# Initial.net
KiCad netlist of a schematic drawn in EAGLE
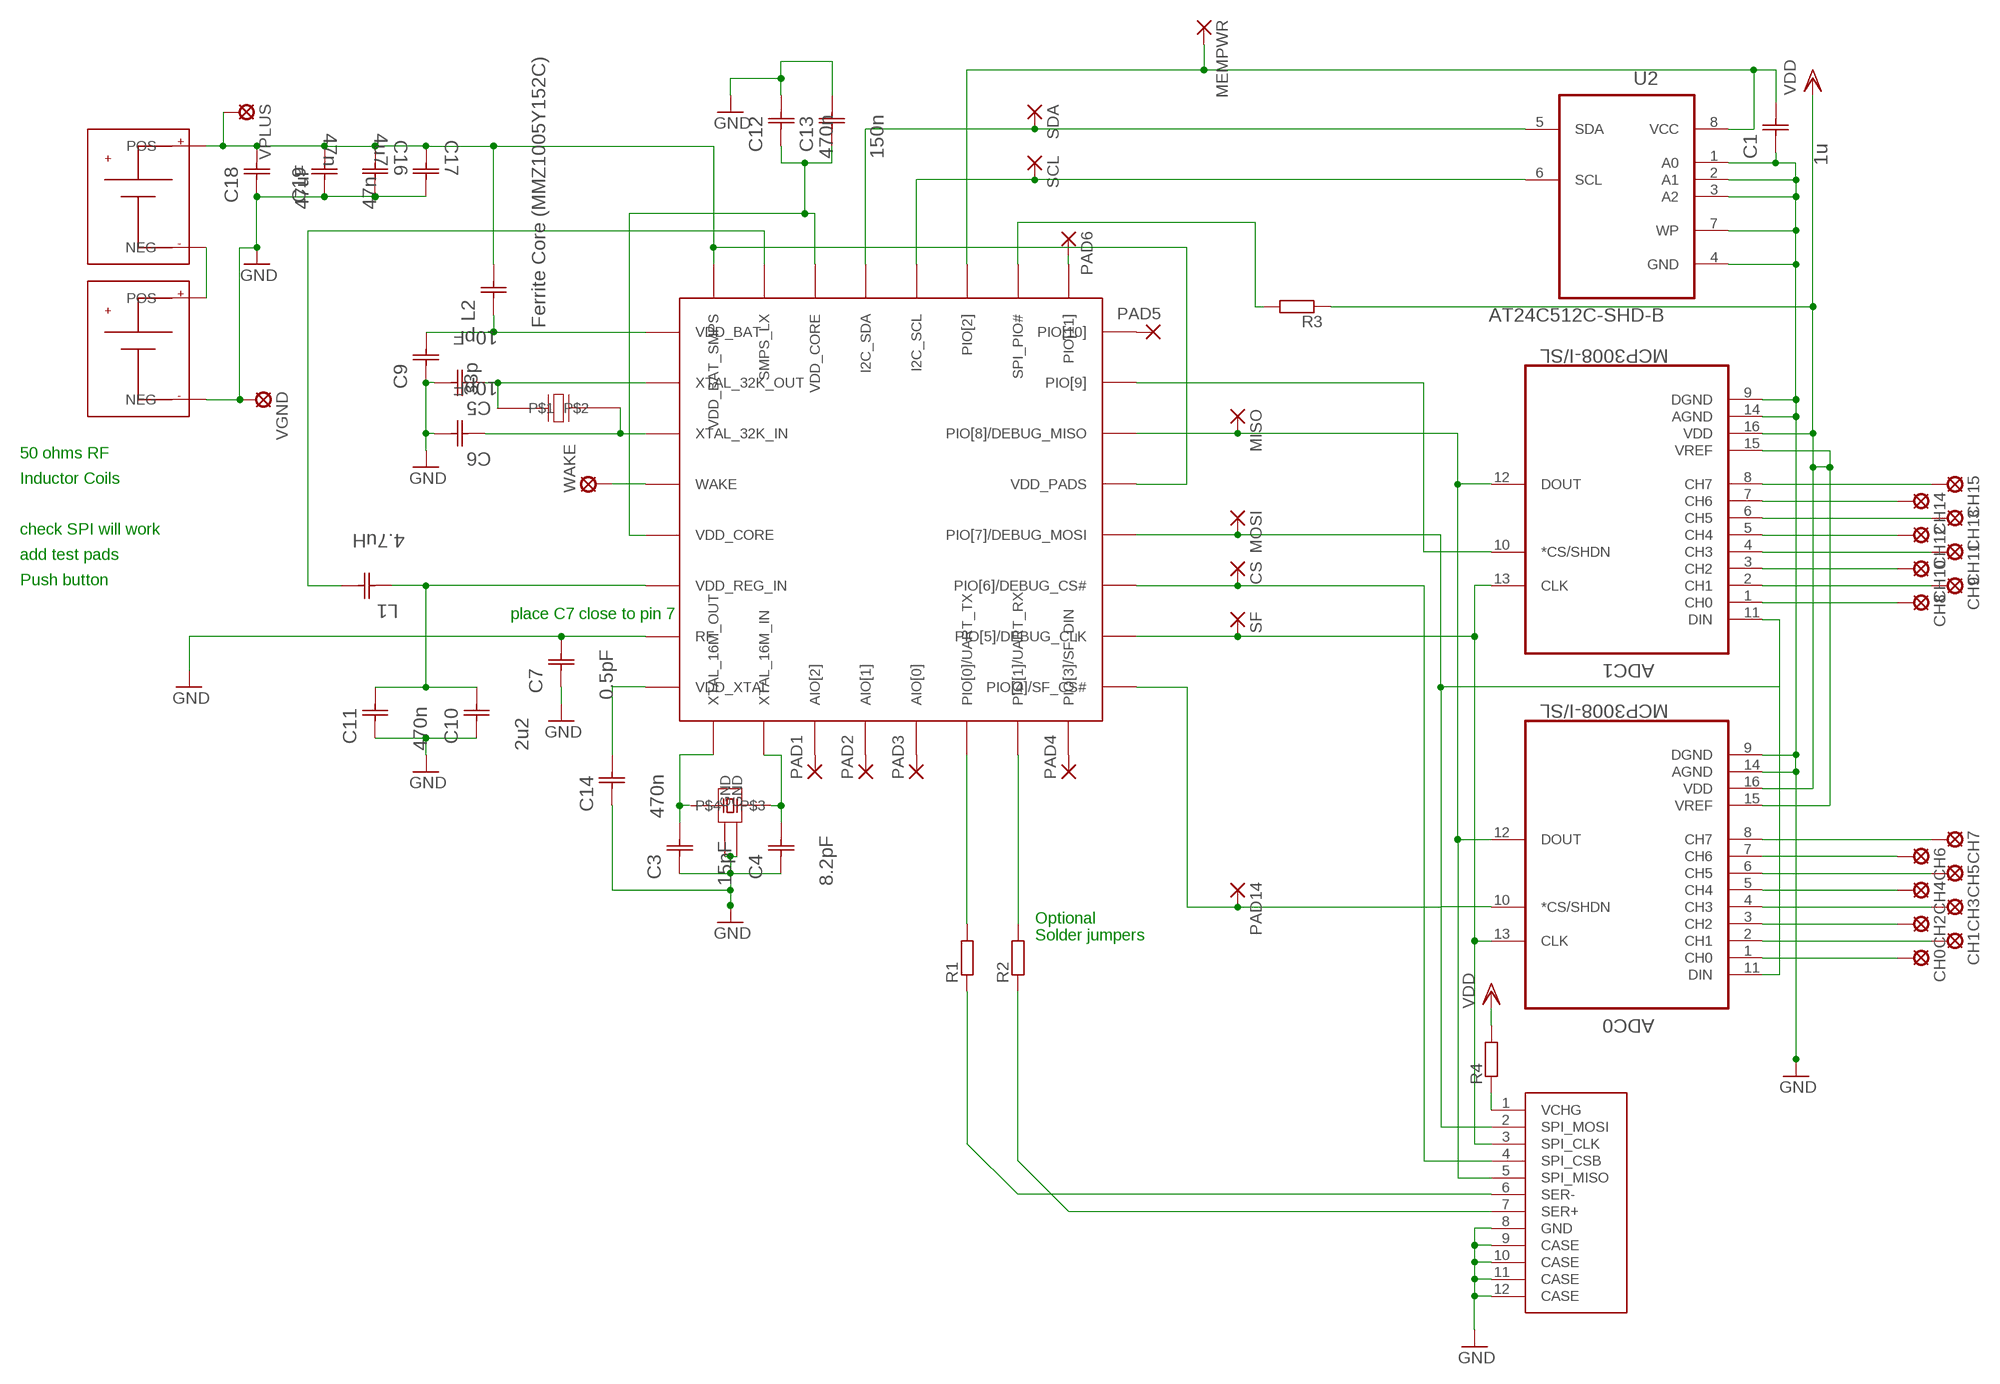
[diagram p0: schematic, sheet 1]

(export (version "E")
  (design (tool "Eeschema 10.0.6"))
  (components
    (comp (ref "ADC0")
      (value "MCP3008-I/SL")
      (footprint "eagle-import:SOIC127P600X175-16N")
      (libsource (lib "eagle-import") (part "MCP3008-I/SL"))
    )
    (comp (ref "ADC1")
      (value "MCP3008-I/SL")
      (footprint "eagle-import:SOIC127P600X175-16N")
      (libsource (lib "eagle-import") (part "MCP3008-I/SL"))
    )
    (comp (ref "C1")
      (value "1u")
      (footprint "eagle-import:CAPC1005X60N")
      (fields (field (name "MPN") "UQCL2A100JAT2A/500") (field (name "TOLERANCE") "±5%"))
      (libsource (lib "eagle-import") (part "UQCL2A100JAT2A/500"))
    )
    (comp (ref "C3")
      (value "15pF")
      (footprint "eagle-import:CAPC1005X60N")
      (fields (field (name "MPN") "UQCL2A150JAT2A/500") (field (name "TOLERANCE") "±5%"))
      (libsource (lib "eagle-import") (part "UQCL2A150JAT2A/500"))
    )
    (comp (ref "C4")
      (value "8.2pF")
      (footprint "eagle-import:CAPC1005X60N")
      (fields (field (name "MPN") "UQCL2A8R2CAT2A/500") (field (name "TOLERANCE") "±.25 pF"))
      (libsource (lib "eagle-import") (part "UQCL2A8R2CAT2A/500"))
    )
    (comp (ref "C5")
      (value "10pF")
      (footprint "eagle-import:CAPC1005X60N")
      (fields (field (name "MPN") "UQCL2A100JAT2A/500") (field (name "TOLERANCE") "±5%"))
      (libsource (lib "eagle-import") (part "UQCL2A100JAT2A/500"))
    )
    (comp (ref "C6")
      (value "10pF")
      (footprint "eagle-import:CAPC1005X60N")
      (fields (field (name "MPN") "UQCL2A100JAT2A/500") (field (name "TOLERANCE") "±5%"))
      (libsource (lib "eagle-import") (part "UQCL2A100JAT2A/500"))
    )
    (comp (ref "C7")
      (value "0.5pF")
      (footprint "eagle-import:CAPC1005X60N")
      (fields (field (name "MPN") "UQCL2A0R5BAT2A/500") (field (name "TOLERANCE") "±.1 pF"))
      (libsource (lib "eagle-import") (part "UQCL2A0R5BAT2A/500"))
    )
    (comp (ref "C9")
      (value "33p")
      (footprint "eagle-import:CAPC1005X60N")
      (fields (field (name "MPN") "UQCL2A100JAT2A/500") (field (name "TOLERANCE") "±5%"))
      (libsource (lib "eagle-import") (part "UQCL2A100JAT2A/500"))
    )
    (comp (ref "C10")
      (value "2u2")
      (footprint "eagle-import:CAPC1005X60N")
      (fields (field (name "MPN") "UQCL2A100JAT2A/500") (field (name "TOLERANCE") "±5%"))
      (libsource (lib "eagle-import") (part "UQCL2A100JAT2A/500"))
    )
    (comp (ref "C11")
      (value "470n")
      (footprint "eagle-import:CAPC1005X60N")
      (fields (field (name "MPN") "UQCL2A100JAT2A/500") (field (name "TOLERANCE") "±5%"))
      (libsource (lib "eagle-import") (part "UQCL2A100JAT2A/500"))
    )
    (comp (ref "C12")
      (value "470n")
      (footprint "eagle-import:CAPC1005X60N")
      (fields (field (name "MPN") "UQCL2A100JAT2A/500") (field (name "TOLERANCE") "±5%"))
      (libsource (lib "eagle-import") (part "UQCL2A100JAT2A/500"))
    )
    (comp (ref "C13")
      (value "150n")
      (footprint "eagle-import:CAPC1005X60N")
      (fields (field (name "MPN") "UQCL2A100JAT2A/500") (field (name "TOLERANCE") "±5%"))
      (libsource (lib "eagle-import") (part "UQCL2A100JAT2A/500"))
    )
    (comp (ref "C14")
      (value "470n")
      (footprint "eagle-import:CAPC1005X60N")
      (fields (field (name "MPN") "UQCL2A100JAT2A/500") (field (name "TOLERANCE") "±5%"))
      (libsource (lib "eagle-import") (part "UQCL2A100JAT2A/500"))
    )
    (comp (ref "C16")
      (value "47n")
      (footprint "eagle-import:CAPC1005X60N")
      (fields (field (name "MPN") "UQCL2A1R0BAT2A/500") (field (name "TOLERANCE") "±.1 pF"))
      (libsource (lib "eagle-import") (part "UQCL2A1R0BAT2A/500"))
    )
    (comp (ref "C17")
      (value "4u7")
      (footprint "eagle-import:CAPC1005X60N")
      (fields (field (name "MPN") "UQCL2A1R0BAT2A/500") (field (name "TOLERANCE") "±.1 pF"))
      (libsource (lib "eagle-import") (part "UQCL2A1R0BAT2A/500"))
    )
    (comp (ref "C18")
      (value "47uF")
      (footprint "eagle-import:CAPC2012X130N")
      (fields (field (name "MPN") "0805AA100MAT1A") (field (name "TOLERANCE") "±20%"))
      (libsource (lib "eagle-import") (part "0805AA100MAT1A"))
    )
    (comp (ref "C19")
      (value "47n")
      (footprint "eagle-import:CAPC2012X130N")
      (fields (field (name "MPN") "0805AA100MAT1A") (field (name "TOLERANCE") "±20%"))
      (libsource (lib "eagle-import") (part "0805AA100MAT1A"))
    )
    (comp (ref "CH0")
      (value "LSP10")
      (footprint "eagle-import:LSP10")
      (libsource (lib "eagle-import") (part "LSP10"))
    )
    (comp (ref "CH1")
      (value "LSP10")
      (footprint "eagle-import:LSP10")
      (libsource (lib "eagle-import") (part "LSP10"))
    )
    (comp (ref "CH2")
      (value "LSP10")
      (footprint "eagle-import:LSP10")
      (libsource (lib "eagle-import") (part "LSP10"))
    )
    (comp (ref "CH3")
      (value "LSP10")
      (footprint "eagle-import:LSP10")
      (libsource (lib "eagle-import") (part "LSP10"))
    )
    (comp (ref "CH4")
      (value "LSP10")
      (footprint "eagle-import:LSP10")
      (libsource (lib "eagle-import") (part "LSP10"))
    )
    (comp (ref "CH5")
      (value "LSP10")
      (footprint "eagle-import:LSP10")
      (libsource (lib "eagle-import") (part "LSP10"))
    )
    (comp (ref "CH6")
      (value "LSP10")
      (footprint "eagle-import:LSP10")
      (libsource (lib "eagle-import") (part "LSP10"))
    )
    (comp (ref "CH7")
      (value "LSP10")
      (footprint "eagle-import:LSP10")
      (libsource (lib "eagle-import") (part "LSP10"))
    )
    (comp (ref "CH8")
      (value "LSP10")
      (footprint "eagle-import:LSP10")
      (libsource (lib "eagle-import") (part "LSP10"))
    )
    (comp (ref "CH9")
      (value "LSP10")
      (footprint "eagle-import:LSP10")
      (libsource (lib "eagle-import") (part "LSP10"))
    )
    (comp (ref "CH10")
      (value "LSP10")
      (footprint "eagle-import:LSP10")
      (libsource (lib "eagle-import") (part "LSP10"))
    )
    (comp (ref "CH11")
      (value "LSP10")
      (footprint "eagle-import:LSP10")
      (libsource (lib "eagle-import") (part "LSP10"))
    )
    (comp (ref "CH12")
      (value "LSP10")
      (footprint "eagle-import:LSP10")
      (libsource (lib "eagle-import") (part "LSP10"))
    )
    (comp (ref "CH13")
      (value "LSP10")
      (footprint "eagle-import:LSP10")
      (libsource (lib "eagle-import") (part "LSP10"))
    )
    (comp (ref "CH14")
      (value "LSP10")
      (footprint "eagle-import:LSP10")
      (libsource (lib "eagle-import") (part "LSP10"))
    )
    (comp (ref "CH15")
      (value "LSP10")
      (footprint "eagle-import:LSP10")
      (libsource (lib "eagle-import") (part "LSP10"))
    )
    (comp (ref "CS")
      (value "1,6/0,8")
      (footprint "eagle-import:1,6_0,8")
      (libsource (lib "eagle-import") (part "1,6/0,8"))
    )
    (comp (ref "L1")
      (value "4.7uH")
      (footprint "eagle-import:CAPC3225X127N")
      (fields (field (name "MPN") "12107C102JAT2A") (field (name "TOLERANCE") "±5%"))
      (libsource (lib "eagle-import") (part "12107C102JAT2A"))
    )
    (comp (ref "L2")
      (value "Ferrite Core (MMZ1005Y152C)")
      (footprint "eagle-import:CAPC1005X60N")
      (fields (field (name "MPN") "UQCL2A100JAT2A/500") (field (name "TOLERANCE") "±5%"))
      (libsource (lib "eagle-import") (part "UQCL2A100JAT2A/500"))
    )
    (comp (ref "MEMPWR")
      (value "1,6/0,8")
      (footprint "eagle-import:1,6_0,8")
      (libsource (lib "eagle-import") (part "1,6/0,8"))
    )
    (comp (ref "MISO")
      (value "1,6/0,8")
      (footprint "eagle-import:1,6_0,8")
      (libsource (lib "eagle-import") (part "1,6/0,8"))
    )
    (comp (ref "MOSI")
      (value "1,6/0,8")
      (footprint "eagle-import:1,6_0,8")
      (libsource (lib "eagle-import") (part "1,6/0,8"))
    )
    (comp (ref "PAD1")
      (value "1,6/0,8")
      (footprint "eagle-import:1,6_0,8")
      (libsource (lib "eagle-import") (part "1,6/0,8"))
    )
    (comp (ref "PAD2")
      (value "1,6/0,8")
      (footprint "eagle-import:1,6_0,8")
      (libsource (lib "eagle-import") (part "1,6/0,8"))
    )
    (comp (ref "PAD3")
      (value "1,6/0,8")
      (footprint "eagle-import:1,6_0,8")
      (libsource (lib "eagle-import") (part "1,6/0,8"))
    )
    (comp (ref "PAD4")
      (value "1,6/0,8")
      (footprint "eagle-import:1,6_0,8")
      (libsource (lib "eagle-import") (part "1,6/0,8"))
    )
    (comp (ref "PAD5")
      (value "1,6/0,8")
      (footprint "eagle-import:1,6_0,8")
      (libsource (lib "eagle-import") (part "1,6/0,8"))
    )
    (comp (ref "PAD6")
      (value "1,6/0,8")
      (footprint "eagle-import:1,6_0,8")
      (libsource (lib "eagle-import") (part "1,6/0,8"))
    )
    (comp (ref "PAD14")
      (value "1,6/0,8")
      (footprint "eagle-import:1,6_0,8")
      (libsource (lib "eagle-import") (part "1,6/0,8"))
    )
    (comp (ref "R1")
      (value "BVS")
      (footprint "eagle-import:BVS")
      (libsource (lib "eagle-import") (part "BVS"))
    )
    (comp (ref "R2")
      (value "BVS")
      (footprint "eagle-import:BVS")
      (libsource (lib "eagle-import") (part "BVS"))
    )
    (comp (ref "R3")
      (value "BVS")
      (footprint "eagle-import:BVS")
      (libsource (lib "eagle-import") (part "BVS"))
    )
    (comp (ref "R4")
      (value "BVS")
      (footprint "eagle-import:BVS")
      (libsource (lib "eagle-import") (part "BVS"))
    )
    (comp (ref "SCL")
      (value "1,6/0,8")
      (footprint "eagle-import:1,6_0,8")
      (libsource (lib "eagle-import") (part "1,6/0,8"))
    )
    (comp (ref "SDA")
      (value "1,6/0,8")
      (footprint "eagle-import:1,6_0,8")
      (libsource (lib "eagle-import") (part "1,6/0,8"))
    )
    (comp (ref "SF")
      (value "1,6/0,8")
      (footprint "eagle-import:1,6_0,8")
      (libsource (lib "eagle-import") (part "1,6/0,8"))
    )
    (comp (ref "U$1")
      (value "CSR1010A05-IQQM-R")
      (footprint "eagle-import:CSR1010A05-IQQM-R")
      (libsource (lib "eagle-import") (part "CSR1010A05-IQQM-R"))
    )
    (comp (ref "U$2")
      (value "8PIN_SMT_CONNECTOR")
      (footprint "eagle-import:8PIN_SMT_CONNECTOR")
      (libsource (lib "eagle-import") (part "8PIN_SMT_CONNECTOR"))
    )
    (comp (ref "U$3")
      (value "TSX3225")
      (footprint "eagle-import:TSX3225")
      (libsource (lib "eagle-import") (part "TSX3225"))
    )
    (comp (ref "U$4")
      (value "SSP-T7-F")
      (footprint "eagle-import:SSP-T7-F")
      (libsource (lib "eagle-import") (part "SSP-T7-F"))
    )
    (comp (ref "U$5")
      (value "BATTERY_2996")
      (footprint "eagle-import:BATTERY_2996")
      (libsource (lib "eagle-import") (part "BATTERY_2996"))
    )
    (comp (ref "U$6")
      (value "BATTERY_2996")
      (footprint "eagle-import:BATTERY_2996")
      (libsource (lib "eagle-import") (part "BATTERY_2996"))
    )
    (comp (ref "U2")
      (value "AT24C512C-SHD-B")
      (footprint "eagle-import:SOIC127P798X216-8N")
      (libsource (lib "eagle-import") (part "AT24C512C-SHD-B"))
    )
    (comp (ref "VGND")
      (value "LSP10")
      (footprint "eagle-import:LSP10")
      (libsource (lib "eagle-import") (part "LSP10"))
    )
    (comp (ref "VPLUS")
      (value "Vrail")
      (footprint "eagle-import:LSP10")
      (libsource (lib "eagle-import") (part "LSP10"))
    )
    (comp (ref "WAKE")
      (value "Vrail")
      (footprint "eagle-import:LSP10")
      (libsource (lib "eagle-import") (part "LSP10"))
    )
  )
  (nets
    (net (code "1") (name "/VCC") (class "Default")
      (node (ref "U2") (pin "8") (pinfunction "VCC_8") (pintype "power_in"))
    )
    (net (code "2") (name "GND") (class "Default")
      (node (ref "ADC0") (pin "14") (pinfunction "AGND_14") (pintype "passive"))
      (node (ref "ADC0") (pin "9") (pinfunction "DGND_9") (pintype "passive"))
      (node (ref "ADC1") (pin "14") (pinfunction "AGND_14") (pintype "passive"))
      (node (ref "ADC1") (pin "9") (pinfunction "DGND_9") (pintype "passive"))
      (node (ref "C1") (pin "2") (pinfunction "C1_2") (pintype "passive"))
      (node (ref "C10") (pin "2") (pinfunction "C1_2") (pintype "passive"))
      (node (ref "C11") (pin "2") (pinfunction "C1_2") (pintype "passive"))
      (node (ref "C12") (pin "1") (pinfunction "C2_1") (pintype "passive"))
      (node (ref "C13") (pin "1") (pinfunction "C2_1") (pintype "passive"))
      (node (ref "C14") (pin "2") (pinfunction "C1_2") (pintype "passive"))
      (node (ref "C16") (pin "1") (pinfunction "C2_1") (pintype "passive"))
      (node (ref "C17") (pin "1") (pinfunction "C2_1") (pintype "passive"))
      (node (ref "C18") (pin "1") (pinfunction "C1_1") (pintype "passive"))
      (node (ref "C19") (pin "1") (pinfunction "C1_1") (pintype "passive"))
      (node (ref "C3") (pin "2") (pinfunction "C1_2") (pintype "passive"))
      (node (ref "C4") (pin "2") (pinfunction "C1_2") (pintype "passive"))
      (node (ref "C5") (pin "1") (pinfunction "C2_1") (pintype "passive"))
      (node (ref "C6") (pin "1") (pinfunction "C2_1") (pintype "passive"))
      (node (ref "C7") (pin "1") (pinfunction "C2_1") (pintype "passive"))
      (node (ref "C7") (pin "2") (pinfunction "C1_2") (pintype "passive"))
      (node (ref "C9") (pin "2") (pinfunction "C1_2") (pintype "passive"))
      (node (ref "U$1") (pin "RF") (pinfunction "RF_RF") (pintype "output"))
      (node (ref "U$2") (pin "10") (pinfunction "CASE_10") (pintype "bidirectional"))
      (node (ref "U$2") (pin "11") (pinfunction "CASE_11") (pintype "bidirectional"))
      (node (ref "U$2") (pin "12") (pinfunction "CASE_12") (pintype "bidirectional"))
      (node (ref "U$2") (pin "8") (pinfunction "GND_8") (pintype "bidirectional"))
      (node (ref "U$2") (pin "9") (pinfunction "CASE_9") (pintype "bidirectional"))
      (node (ref "U$3") (pin "2") (pinfunction "GND_2") (pintype "bidirectional"))
      (node (ref "U$3") (pin "4") (pinfunction "GND_4") (pintype "bidirectional"))
      (node (ref "U$6") (pin "NEG") (pinfunction "NEG_NEG") (pintype "bidirectional"))
      (node (ref "U2") (pin "1") (pinfunction "A0_1") (pintype "input"))
      (node (ref "U2") (pin "2") (pinfunction "A1_2") (pintype "input"))
      (node (ref "U2") (pin "3") (pinfunction "A2_3") (pintype "input"))
      (node (ref "U2") (pin "4") (pinfunction "GND_4") (pintype "power_in"))
      (node (ref "U2") (pin "7") (pinfunction "WP_7") (pintype "input"))
      (node (ref "VGND") (pin "MP") (pinfunction "MP_MP") (pintype "passive"))
    )
    (net (code "3") (name "Net-(ADC0-*CS{slash}SHDN)") (class "Default")
      (node (ref "ADC0") (pin "10") (pinfunction "*CS/SHDN_10") (pintype "input"))
      (node (ref "PAD14") (pin "1") (pinfunction "P_1") (pintype "passive"))
      (node (ref "U$1") (pin "PIO[4]/SF_CS#") (pinfunction "PIO[4]/SF_CS#_PIO[4]/SF_CS#") (pintype "output"))
    )
    (net (code "4") (name "Net-(ADC0-CH0)") (class "Default")
      (node (ref "ADC0") (pin "1") (pinfunction "CH0_1") (pintype "input"))
      (node (ref "CH0") (pin "MP") (pinfunction "MP_MP") (pintype "passive"))
    )
    (net (code "5") (name "Net-(ADC0-CH1)") (class "Default")
      (node (ref "ADC0") (pin "2") (pinfunction "CH1_2") (pintype "input"))
      (node (ref "CH1") (pin "MP") (pinfunction "MP_MP") (pintype "passive"))
    )
    (net (code "6") (name "Net-(ADC0-CH2)") (class "Default")
      (node (ref "ADC0") (pin "3") (pinfunction "CH2_3") (pintype "input"))
      (node (ref "CH2") (pin "MP") (pinfunction "MP_MP") (pintype "passive"))
    )
    (net (code "7") (name "Net-(ADC0-CH3)") (class "Default")
      (node (ref "ADC0") (pin "4") (pinfunction "CH3_4") (pintype "input"))
      (node (ref "CH3") (pin "MP") (pinfunction "MP_MP") (pintype "passive"))
    )
    (net (code "8") (name "Net-(ADC0-CH4)") (class "Default")
      (node (ref "ADC0") (pin "5") (pinfunction "CH4_5") (pintype "input"))
      (node (ref "CH4") (pin "MP") (pinfunction "MP_MP") (pintype "passive"))
    )
    (net (code "9") (name "Net-(ADC0-CH5)") (class "Default")
      (node (ref "ADC0") (pin "6") (pinfunction "CH5_6") (pintype "input"))
      (node (ref "CH5") (pin "MP") (pinfunction "MP_MP") (pintype "passive"))
    )
    (net (code "10") (name "Net-(ADC0-CH6)") (class "Default")
      (node (ref "ADC0") (pin "7") (pinfunction "CH6_7") (pintype "input"))
      (node (ref "CH6") (pin "MP") (pinfunction "MP_MP") (pintype "passive"))
    )
    (net (code "11") (name "Net-(ADC0-CH7)") (class "Default")
      (node (ref "ADC0") (pin "8") (pinfunction "CH7_8") (pintype "input"))
      (node (ref "CH7") (pin "MP") (pinfunction "MP_MP") (pintype "passive"))
    )
    (net (code "12") (name "Net-(ADC0-CLK)") (class "Default")
      (node (ref "ADC0") (pin "13") (pinfunction "CLK_13") (pintype "input"))
      (node (ref "ADC1") (pin "13") (pinfunction "CLK_13") (pintype "input"))
      (node (ref "SF") (pin "1") (pinfunction "P_1") (pintype "passive"))
      (node (ref "U$1") (pin "PIO[5]/DEBUG_CLK") (pinfunction "PIO[5]/DEBUG_CLK_PIO[5]/DEBUG_CLK") (pintype "output"))
      (node (ref "U$2") (pin "3") (pinfunction "SPI_CLK_3") (pintype "bidirectional"))
    )
    (net (code "13") (name "Net-(ADC0-DIN)") (class "Default")
      (node (ref "ADC0") (pin "11") (pinfunction "DIN_11") (pintype "input"))
      (node (ref "ADC1") (pin "11") (pinfunction "DIN_11") (pintype "input"))
      (node (ref "MOSI") (pin "1") (pinfunction "P_1") (pintype "passive"))
      (node (ref "U$1") (pin "PIO[7]/DEBUG_MOSI") (pinfunction "PIO[7]/DEBUG_MOSI_PIO[7]/DEBUG_MOSI") (pintype "output"))
      (node (ref "U$2") (pin "2") (pinfunction "SPI_MOSI_2") (pintype "bidirectional"))
    )
    (net (code "14") (name "Net-(ADC0-DOUT)") (class "Default")
      (node (ref "ADC0") (pin "12") (pinfunction "DOUT_12") (pintype "output"))
      (node (ref "ADC1") (pin "12") (pinfunction "DOUT_12") (pintype "output"))
      (node (ref "MISO") (pin "1") (pinfunction "P_1") (pintype "passive"))
      (node (ref "U$1") (pin "PIO[8]/DEBUG_MISO") (pinfunction "PIO[8]/DEBUG_MISO_PIO[8]/DEBUG_MISO") (pintype "output"))
      (node (ref "U$2") (pin "5") (pinfunction "SPI_MISO_5") (pintype "bidirectional"))
    )
    (net (code "15") (name "Net-(ADC1-*CS{slash}SHDN)") (class "Default")
      (node (ref "ADC1") (pin "10") (pinfunction "*CS/SHDN_10") (pintype "input"))
      (node (ref "U$1") (pin "PIO[9]") (pinfunction "PIO[9]_PIO[9]") (pintype "output"))
    )
    (net (code "16") (name "Net-(ADC1-CH0)") (class "Default")
      (node (ref "ADC1") (pin "1") (pinfunction "CH0_1") (pintype "input"))
      (node (ref "CH8") (pin "MP") (pinfunction "MP_MP") (pintype "passive"))
    )
    (net (code "17") (name "Net-(ADC1-CH1)") (class "Default")
      (node (ref "ADC1") (pin "2") (pinfunction "CH1_2") (pintype "input"))
      (node (ref "CH9") (pin "MP") (pinfunction "MP_MP") (pintype "passive"))
    )
    (net (code "18") (name "Net-(ADC1-CH2)") (class "Default")
      (node (ref "ADC1") (pin "3") (pinfunction "CH2_3") (pintype "input"))
      (node (ref "CH10") (pin "MP") (pinfunction "MP_MP") (pintype "passive"))
    )
    (net (code "19") (name "Net-(ADC1-CH3)") (class "Default")
      (node (ref "ADC1") (pin "4") (pinfunction "CH3_4") (pintype "input"))
      (node (ref "CH11") (pin "MP") (pinfunction "MP_MP") (pintype "passive"))
    )
    (net (code "20") (name "Net-(ADC1-CH4)") (class "Default")
      (node (ref "ADC1") (pin "5") (pinfunction "CH4_5") (pintype "input"))
      (node (ref "CH12") (pin "MP") (pinfunction "MP_MP") (pintype "passive"))
    )
    (net (code "21") (name "Net-(ADC1-CH5)") (class "Default")
      (node (ref "ADC1") (pin "6") (pinfunction "CH5_6") (pintype "input"))
      (node (ref "CH13") (pin "MP") (pinfunction "MP_MP") (pintype "passive"))
    )
    (net (code "22") (name "Net-(ADC1-CH6)") (class "Default")
      (node (ref "ADC1") (pin "7") (pinfunction "CH6_7") (pintype "input"))
      (node (ref "CH14") (pin "MP") (pinfunction "MP_MP") (pintype "passive"))
    )
    (net (code "23") (name "Net-(ADC1-CH7)") (class "Default")
      (node (ref "ADC1") (pin "8") (pinfunction "CH7_8") (pintype "input"))
      (node (ref "CH15") (pin "MP") (pinfunction "MP_MP") (pintype "passive"))
    )
    (net (code "24") (name "Net-(C1-C2)") (class "Default")
      (node (ref "C1") (pin "1") (pinfunction "C2_1") (pintype "passive"))
      (node (ref "MEMPWR") (pin "1") (pinfunction "P_1") (pintype "passive"))
      (node (ref "U$1") (pin "PIO[2]") (pinfunction "PIO[2]_PIO[2]") (pintype "output"))
    )
    (net (code "25") (name "Net-(C3-C2)") (class "Default")
      (node (ref "C3") (pin "1") (pinfunction "C2_1") (pintype "passive"))
      (node (ref "U$1") (pin "XTAL_16M_OUT") (pinfunction "XTAL_16M_OUT_XTAL_16M_OUT") (pintype "output"))
    )
    (net (code "26") (name "Net-(C4-C2)") (class "Default")
      (node (ref "C4") (pin "1") (pinfunction "C2_1") (pintype "passive"))
      (node (ref "U$1") (pin "XTAL_16M_IN") (pinfunction "XTAL_16M_IN_XTAL_16M_IN") (pintype "output"))
    )
    (net (code "27") (name "Net-(C5-C1)") (class "Default")
      (node (ref "C5") (pin "2") (pinfunction "C1_2") (pintype "passive"))
      (node (ref "U$1") (pin "XTAL_32K_OUT") (pinfunction "XTAL_32K_OUT_XTAL_32K_OUT") (pintype "output"))
    )
    (net (code "28") (name "Net-(C6-C1)") (class "Default")
      (node (ref "C6") (pin "2") (pinfunction "C1_2") (pintype "passive"))
      (node (ref "U$1") (pin "XTAL_32K_IN") (pinfunction "XTAL_32K_IN_XTAL_32K_IN") (pintype "output"))
      (node (ref "U$4") (pin "1") (pinfunction "P$1_1") (pintype "bidirectional"))
    )
    (net (code "29") (name "Net-(C9-C2)") (class "Default")
      (node (ref "C9") (pin "1") (pinfunction "C2_1") (pintype "passive"))
      (node (ref "L2") (pin "2") (pinfunction "C1_2") (pintype "passive"))
      (node (ref "U$1") (pin "VDD_BAT") (pinfunction "VDD_BAT_VDD_BAT") (pintype "output"))
    )
    (net (code "30") (name "Net-(C10-C2)") (class "Default")
      (node (ref "C10") (pin "1") (pinfunction "C2_1") (pintype "passive"))
      (node (ref "C11") (pin "1") (pinfunction "C2_1") (pintype "passive"))
      (node (ref "L1") (pin "1") (pinfunction "C1_1") (pintype "passive"))
      (node (ref "U$1") (pin "VDD_REG_IN") (pinfunction "VDD_REG_IN_VDD_REG_IN") (pintype "output"))
    )
    (net (code "31") (name "Net-(C12-C1)") (class "Default")
      (node (ref "C12") (pin "2") (pinfunction "C1_2") (pintype "passive"))
      (node (ref "C13") (pin "2") (pinfunction "C1_2") (pintype "passive"))
      (node (ref "U$1") (pin "VDD_CORE") (pinfunction "VDD_CORE_VDD_CORE") (pintype "output"))
      (node (ref "U$1") (pin "VDD_CORE@1") (pinfunction "VDD_CORE_VDD_CORE@1") (pintype "bidirectional"))
    )
    (net (code "32") (name "Net-(C14-C2)") (class "Default")
      (node (ref "C14") (pin "1") (pinfunction "C2_1") (pintype "passive"))
      (node (ref "U$1") (pin "VDD_XTAL") (pinfunction "VDD_XTAL_VDD_XTAL") (pintype "output"))
    )
    (net (code "33") (name "Net-(C16-C1)") (class "Default")
      (node (ref "C16") (pin "2") (pinfunction "C1_2") (pintype "passive"))
      (node (ref "C17") (pin "2") (pinfunction "C1_2") (pintype "passive"))
      (node (ref "C18") (pin "2") (pinfunction "C2_2") (pintype "passive"))
      (node (ref "C19") (pin "2") (pinfunction "C2_2") (pintype "passive"))
      (node (ref "L2") (pin "1") (pinfunction "C2_1") (pintype "passive"))
      (node (ref "U$1") (pin "VDD_BAT_SMPS") (pinfunction "VDD_BAT_SMPS_VDD_BAT_SMPS") (pintype "output"))
      (node (ref "U$1") (pin "VDD_PADS") (pinfunction "VDD_PADS_VDD_PADS") (pintype "output"))
      (node (ref "U$5") (pin "POS@1") (pinfunction "POS_POS@1") (pintype "bidirectional"))
      (node (ref "VPLUS") (pin "MP") (pinfunction "MP_MP") (pintype "passive"))
    )
    (net (code "34") (name "Net-(CS-P)") (class "Default")
      (node (ref "CS") (pin "1") (pinfunction "P_1") (pintype "passive"))
      (node (ref "U$1") (pin "PIO[6]/DEBUG_CS#") (pinfunction "PIO[6]/DEBUG_CS#_PIO[6]/DEBUG_CS#") (pintype "output"))
      (node (ref "U$2") (pin "4") (pinfunction "SPI_CSB_4") (pintype "bidirectional"))
    )
    (net (code "35") (name "Net-(L1-C2)") (class "Default")
      (node (ref "L1") (pin "2") (pinfunction "C2_2") (pintype "passive"))
      (node (ref "U$1") (pin "SMPS_LX") (pinfunction "SMPS_LX_SMPS_LX") (pintype "output"))
    )
    (net (code "36") (name "Net-(PAD1-P)") (class "Default")
      (node (ref "PAD1") (pin "1") (pinfunction "P_1") (pintype "passive"))
      (node (ref "U$1") (pin "AIO[2]") (pinfunction "AIO[2]_AIO[2]") (pintype "output"))
    )
    (net (code "37") (name "Net-(PAD2-P)") (class "Default")
      (node (ref "PAD2") (pin "1") (pinfunction "P_1") (pintype "passive"))
      (node (ref "U$1") (pin "AIO[1]") (pinfunction "AIO[1]_AIO[1]") (pintype "output"))
    )
    (net (code "38") (name "Net-(PAD3-P)") (class "Default")
      (node (ref "PAD3") (pin "1") (pinfunction "P_1") (pintype "passive"))
      (node (ref "U$1") (pin "AIO[0]") (pinfunction "AIO[0]_AIO[0]") (pintype "output"))
    )
    (net (code "39") (name "Net-(PAD4-P)") (class "Default")
      (node (ref "PAD4") (pin "1") (pinfunction "P_1") (pintype "passive"))
      (node (ref "U$1") (pin "PIO[3]/SF_DIN") (pinfunction "PIO[3]/SF_DIN_PIO[3]/SF_DIN") (pintype "output"))
    )
    (net (code "40") (name "Net-(PAD5-P)") (class "Default")
      (node (ref "PAD5") (pin "1") (pinfunction "P_1") (pintype "passive"))
      (node (ref "U$1") (pin "PIO[10]") (pinfunction "PIO[10]_PIO[10]") (pintype "output"))
    )
    (net (code "41") (name "Net-(PAD6-P)") (class "Default")
      (node (ref "PAD6") (pin "1") (pinfunction "P_1") (pintype "passive"))
      (node (ref "U$1") (pin "PIO[11]") (pinfunction "PIO[11]_PIO[11]") (pintype "output"))
    )
    (net (code "42") (name "Net-(R1-Pad1)") (class "Default")
      (node (ref "R1") (pin "1") (pinfunction "1_1") (pintype "passive"))
      (node (ref "U$1") (pin "PIO[0]/UART_TX") (pinfunction "PIO[0]/UART_TX_PIO[0]/UART_TX") (pintype "output"))
    )
    (net (code "43") (name "Net-(R2-Pad1)") (class "Default")
      (node (ref "R2") (pin "1") (pinfunction "1_1") (pintype "passive"))
      (node (ref "U$1") (pin "PIO[1]/UART_RX") (pinfunction "PIO[1]/UART_RX_PIO[1]/UART_RX") (pintype "output"))
    )
    (net (code "44") (name "Net-(R3-Pad1)") (class "Default")
      (node (ref "R3") (pin "1") (pinfunction "1_1") (pintype "passive"))
      (node (ref "U$1") (pin "SPI_PIO#") (pinfunction "SPI_PIO#_SPI_PIO#") (pintype "output"))
    )
    (net (code "45") (name "Net-(SCL-P)") (class "Default")
      (node (ref "SCL") (pin "1") (pinfunction "P_1") (pintype "passive"))
      (node (ref "U$1") (pin "I2C_SCL") (pinfunction "I2C_SCL_I2C_SCL") (pintype "output"))
      (node (ref "U2") (pin "6") (pinfunction "SCL_6") (pintype "input"))
    )
    (net (code "46") (name "Net-(SDA-P)") (class "Default")
      (node (ref "SDA") (pin "1") (pinfunction "P_1") (pintype "passive"))
      (node (ref "U$1") (pin "I2C_SDA") (pinfunction "I2C_SDA_I2C_SDA") (pintype "output"))
      (node (ref "U2") (pin "5") (pinfunction "SDA_5") (pintype "bidirectional"))
    )
    (net (code "47") (name "Net-(U$1-PadWAKE)") (class "Default")
      (node (ref "U$1") (pin "WAKE") (pinfunction "WAKE_WAKE") (pintype "output"))
      (node (ref "WAKE") (pin "MP") (pinfunction "MP_MP") (pintype "passive"))
    )
    (net (code "48") (name "Net-(U$2-SER+)") (class "Default")
      (node (ref "R2") (pin "2") (pinfunction "2_2") (pintype "passive"))
      (node (ref "U$2") (pin "7") (pinfunction "SER+_7") (pintype "bidirectional"))
    )
    (net (code "49") (name "Net-(U$2-SER-)") (class "Default")
      (node (ref "R1") (pin "2") (pinfunction "2_2") (pintype "passive"))
      (node (ref "U$2") (pin "6") (pinfunction "SER-_6") (pintype "bidirectional"))
    )
    (net (code "50") (name "Net-(U$2-VCHG)") (class "Default")
      (node (ref "R4") (pin "2") (pinfunction "2_2") (pintype "passive"))
      (node (ref "U$2") (pin "1") (pinfunction "VCHG_1") (pintype "bidirectional"))
    )
    (net (code "51") (name "Net-(U$6-POS)") (class "Default")
      (node (ref "U$5") (pin "NEG") (pinfunction "NEG_NEG") (pintype "bidirectional"))
      (node (ref "U$6") (pin "POS@1") (pinfunction "POS_POS@1") (pintype "bidirectional"))
    )
    (net (code "52") (name "VDD") (class "Default")
      (node (ref "ADC0") (pin "15") (pinfunction "VREF_15") (pintype "input"))
      (node (ref "ADC0") (pin "16") (pinfunction "VDD_16") (pintype "power_in"))
      (node (ref "ADC1") (pin "15") (pinfunction "VREF_15") (pintype "input"))
      (node (ref "ADC1") (pin "16") (pinfunction "VDD_16") (pintype "power_in"))
      (node (ref "R3") (pin "2") (pinfunction "2_2") (pintype "passive"))
      (node (ref "R4") (pin "1") (pinfunction "1_1") (pintype "passive"))
    )
    (net (code "53") (name "unconnected-(U$3-P$3-Pad1)") (class "Default")
      (node (ref "U$3") (pin "1") (pinfunction "P$3_1") (pintype "bidirectional"))
    )
    (net (code "54") (name "unconnected-(U$3-P$4-Pad3)") (class "Default")
      (node (ref "U$3") (pin "3") (pinfunction "P$4_3") (pintype "bidirectional"))
    )
    (net (code "55") (name "unconnected-(U$4-P$2-Pad4)") (class "Default")
      (node (ref "U$4") (pin "4") (pinfunction "P$2_4") (pintype "bidirectional"))
    )
  )
)
